# Power.net
KiCad netlist of a schematic drawn in Altium Designer
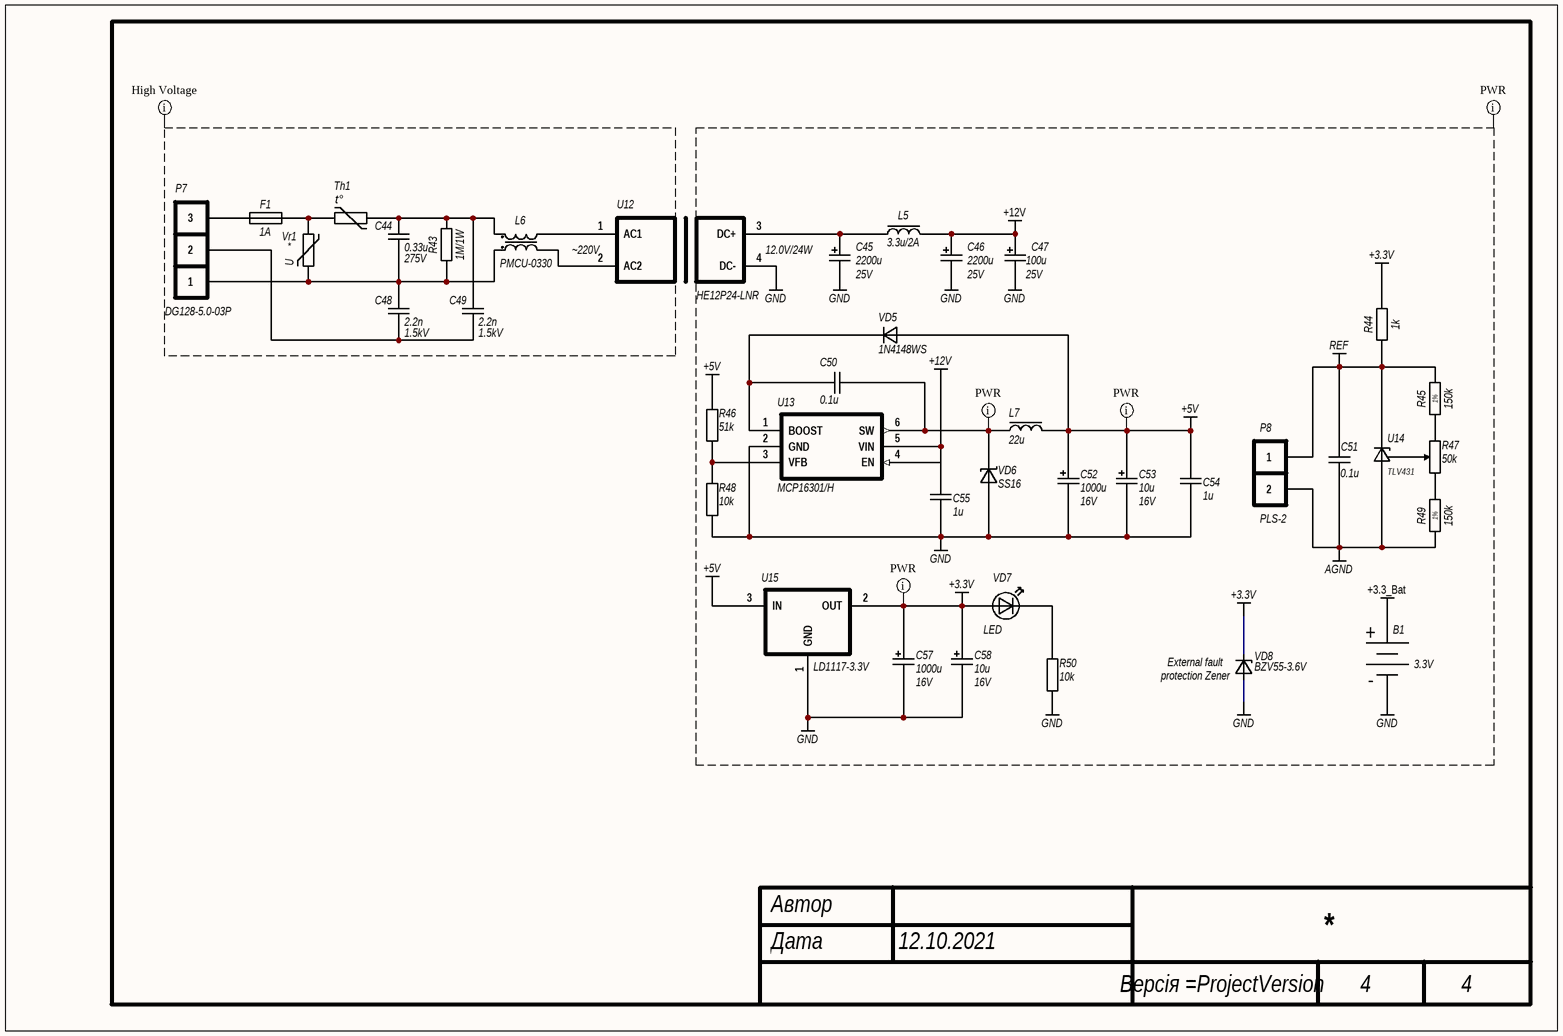
[diagram p0: Power.SchDoc]

(export (version "E")
  (design (tool "Eeschema 10.0.6"))
  (components
    (comp (ref "B1")
      (value "3.3V")
      (footprint "BH810")
      (description "Battery holder CR2032 (3.3В)")
      (libsource (lib "Passive") (part "Battery Holder"))
    )
    (comp (ref "C44")
      (value "0.33u")
      (footprint "MER 13x5.5 h10 R10.16")
      (fields (field (name "VOLTAGE") "275V"))
      (libsource (lib "Passive") (part "Capasitor"))
    )
    (comp (ref "C45")
      (value "2200u")
      (footprint "El-d13-h25-F5-0.6")
      (fields (field (name "VOLTAGE") "25V"))
      (libsource (lib "Passive") (part "Capasitor POL"))
    )
    (comp (ref "C46")
      (value "2200u")
      (footprint "El-d13-h25-F5-0.6")
      (fields (field (name "VOLTAGE") "25V"))
      (libsource (lib "Passive") (part "Capasitor POL"))
    )
    (comp (ref "C47")
      (value "100u")
      (footprint "EL Case A (3216-18)")
      (fields (field (name "VOLTAGE") "25V"))
      (libsource (lib "Passive") (part "Capasitor TECAP"))
    )
    (comp (ref "C48")
      (value "2.2n")
      (footprint "MER 13x5.5 h10 R10.16")
      (fields (field (name "VOLTAGE") "1.5kV"))
      (libsource (lib "Passive") (part "Capasitor"))
    )
    (comp (ref "C49")
      (value "2.2n")
      (footprint "MER 13x5.5 h10 R10.16")
      (fields (field (name "VOLTAGE") "1.5kV"))
      (libsource (lib "Passive") (part "Capasitor"))
    )
    (comp (ref "C50")
      (value "0.1u")
      (footprint "C0603(1608)")
      (libsource (lib "Passive") (part "Capasitor SMD"))
    )
    (comp (ref "C51")
      (value "0.1u")
      (footprint "C0603(1608)")
      (libsource (lib "Passive") (part "Capasitor SMD"))
    )
    (comp (ref "C52")
      (value "1000u")
      (footprint "El-d10-h16-F5-0.6")
      (fields (field (name "VOLTAGE") "16V"))
      (libsource (lib "Passive") (part "Capasitor POL"))
    )
    (comp (ref "C53")
      (value "10u")
      (footprint "EL Case A (3216-18)")
      (fields (field (name "VOLTAGE") "16V"))
      (libsource (lib "Passive") (part "Capasitor TECAP"))
    )
    (comp (ref "C54")
      (value "1u")
      (footprint "C0603(1608)")
      (libsource (lib "Passive") (part "Capasitor SMD"))
    )
    (comp (ref "C55")
      (value "1u")
      (footprint "C0603(1608)")
      (libsource (lib "Passive") (part "Capasitor SMD"))
    )
    (comp (ref "C57")
      (value "1000u")
      (footprint "El-d10-h16-F5-0.6")
      (fields (field (name "VOLTAGE") "16V"))
      (libsource (lib "Passive") (part "Capasitor POL"))
    )
    (comp (ref "C58")
      (value "10u")
      (footprint "EL Case A (3216-18)")
      (fields (field (name "VOLTAGE") "16V"))
      (libsource (lib "Passive") (part "Capasitor TECAP"))
    )
    (comp (ref "F1") (value "1A") (footprint "562 Series") (libsource (lib "Passive") (part "Fuse")))
    (comp (ref "L5") (value "3.3u/2A") (footprint "DR-CW8A") (libsource (lib "") (part "Inductor_1")))
    (comp (ref "L6") (value "~") (footprint "PMCU-0330") (libsource (lib "Passive") (part "Chocke Inductor")))
    (comp (ref "L7") (value "22u") (footprint "CDRH6D28") (libsource (lib "Passive") (part "Inductor")))
    (comp (ref "P7")
      (value "DG128-5.0-03P")
      (footprint "DG128-5.0-03P")
      (description "20A/300V AC 5mm")
      (libsource (lib "Connector") (part "DG128-5.0-03P"))
    )
    (comp (ref "P8") (value "PLS-2") (footprint "PLS-2") (libsource (lib "Connector") (part "PLS-2")))
    (comp (ref "R43")
      (value "1M/1W")
      (footprint "RES1016-650X250")
      (libsource (lib "Passive") (part "Resistor THD"))
    )
    (comp (ref "R44") (value "1k") (footprint "R0603") (libsource (lib "Passive") (part "Resistor SMD")))
    (comp (ref "R45")
      (value "150k")
      (footprint "R0603")
      (fields (field (name "ACCURACY") "1%"))
      (libsource (lib "Passive") (part "Resistor SMD"))
    )
    (comp (ref "R46") (value "51k") (footprint "R0603") (libsource (lib "Passive") (part "Resistor SMD")))
    (comp (ref "R47")
      (value "50k")
      (footprint "T910W (3296W)")
      (libsource (lib "Passive") (part "Trimming Resistor"))
    )
    (comp (ref "R48") (value "10k") (footprint "R0603") (libsource (lib "Passive") (part "Resistor SMD")))
    (comp (ref "R49")
      (value "150k")
      (footprint "R0603")
      (fields (field (name "ACCURACY") "1%"))
      (libsource (lib "Passive") (part "Resistor SMD"))
    )
    (comp (ref "R50") (value "10k") (footprint "R0603") (libsource (lib "Passive") (part "Resistor SMD")))
    (comp (ref "Th1") (value "~") (footprint "TH D13 7.5b") (libsource (lib "Passive") (part "Thermistor")))
    (comp (ref "U12")
      (value "HE12P24-LNR")
      (footprint "HExxPyy-LRN")
      (fields (field (name "OUT") "12.0V/24W") (field (name "IN") "~220V"))
      (libsource (lib "Power") (part "HE12P24-LNR"))
    )
    (comp (ref "U13")
      (value "MCP16301/H")
      (footprint "SOT23-6")
      (libsource (lib "Power") (part "MCP16301/H"))
    )
    (comp (ref "U14") (value "TLV431") (footprint "SOT23") (libsource (lib "Diode") (part "TL431")))
    (comp (ref "U15") (value "LD1117-3.3V") (footprint "SOT223") (libsource (lib "Power") (part "LD1117")))
    (comp (ref "VD5")
      (value "1N4148WS")
      (footprint "SOD323")
      (description "SOD323 100V 200mA")
      (libsource (lib "Diode") (part "1N4148WS"))
    )
    (comp (ref "VD6")
      (value "SS16")
      (footprint "DO-214AC (SMA)")
      (description "SMA (DO214AC) Schottky 60V 1A")
      (libsource (lib "Diode") (part "SS16"))
    )
    (comp (ref "VD7") (value "LED") (footprint "SMD_0805_GREEN") (libsource (lib "Diode") (part "LED")))
    (comp (ref "VD8")
      (value "BZV55-3.6V")
      (footprint "SOD80C")
      (description "SOD80C 250mA")
      (fields (field (name "VOLTAGE") "3.6V"))
      (libsource (lib "Diode") (part "BZV55"))
    )
    (comp (ref "Vr1") (value "*") (footprint "VAR-10K-5.6") (libsource (lib "Passive") (part "Varistor")))
  )
  (nets
    (net (code "1") (name "+3.3V") (class "Default")
      (node (ref "C57") (pin "1") (pinfunction "1_1") (pintype "passive"))
      (node (ref "C58") (pin "1") (pinfunction "1_1") (pintype "passive"))
      (node (ref "R44") (pin "2") (pinfunction "2_2") (pintype "passive"))
      (node (ref "U15") (pin "2") (pinfunction "OUT_2") (pintype "power_in"))
      (node (ref "VD7") (pin "1") (pinfunction "A_1") (pintype "passive"))
      (node (ref "VD8") (pin "2") (pinfunction "K_2") (pintype "passive"))
    )
    (net (code "2") (name "+3.3_Bat") (class "Default")
      (node (ref "B1") (pin "1") (pinfunction "1_1") (pintype "passive"))
    )
    (net (code "3") (name "+5V") (class "Default")
      (node (ref "C52") (pin "1") (pinfunction "1_1") (pintype "passive"))
      (node (ref "C53") (pin "1") (pinfunction "1_1") (pintype "passive"))
      (node (ref "C54") (pin "1") (pinfunction "1_1") (pintype "passive"))
      (node (ref "L7") (pin "2") (pinfunction "2_2") (pintype "passive"))
      (node (ref "R46") (pin "2") (pinfunction "2_2") (pintype "passive"))
      (node (ref "U15") (pin "3") (pinfunction "IN_3") (pintype "power_in"))
      (node (ref "VD5") (pin "1") (pinfunction "A_1") (pintype "passive"))
    )
    (net (code "4") (name "+12V") (class "Default")
      (node (ref "C46") (pin "1") (pinfunction "1_1") (pintype "passive"))
      (node (ref "C47") (pin "1") (pinfunction "1_1") (pintype "passive"))
      (node (ref "C55") (pin "1") (pinfunction "1_1") (pintype "passive"))
      (node (ref "L5") (pin "2") (pinfunction "2_2") (pintype "passive"))
      (node (ref "U13") (pin "4") (pinfunction "EN_4") (pintype "input"))
      (node (ref "U13") (pin "5") (pinfunction "VIN_5") (pintype "power_in"))
    )
    (net (code "5") (name "AGND") (class "Default")
      (node (ref "C51") (pin "1") (pinfunction "1_1") (pintype "passive"))
      (node (ref "P8") (pin "2") (pinfunction "2_2") (pintype "passive"))
      (node (ref "R49") (pin "1") (pinfunction "1_1") (pintype "passive"))
      (node (ref "U14") (pin "1") (pinfunction "A_1") (pintype "passive"))
    )
    (net (code "6") (name "GND") (class "Default")
      (node (ref "B1") (pin "2") (pinfunction "2_2") (pintype "passive"))
      (node (ref "C45") (pin "2") (pinfunction "2_2") (pintype "passive"))
      (node (ref "C46") (pin "2") (pinfunction "2_2") (pintype "passive"))
      (node (ref "C47") (pin "2") (pinfunction "2_2") (pintype "passive"))
      (node (ref "C52") (pin "2") (pinfunction "2_2") (pintype "passive"))
      (node (ref "C53") (pin "2") (pinfunction "2_2") (pintype "passive"))
      (node (ref "C54") (pin "2") (pinfunction "2_2") (pintype "passive"))
      (node (ref "C55") (pin "2") (pinfunction "2_2") (pintype "passive"))
      (node (ref "C57") (pin "2") (pinfunction "2_2") (pintype "passive"))
      (node (ref "C58") (pin "2") (pinfunction "2_2") (pintype "passive"))
      (node (ref "R48") (pin "1") (pinfunction "1_1") (pintype "passive"))
      (node (ref "R50") (pin "1") (pinfunction "1_1") (pintype "passive"))
      (node (ref "U12") (pin "4") (pinfunction "DC-_4") (pintype "passive"))
      (node (ref "U13") (pin "2") (pinfunction "GND_2") (pintype "power_in"))
      (node (ref "U15") (pin "1") (pinfunction "GND_1") (pintype "power_in"))
      (node (ref "VD6") (pin "1") (pinfunction "A_1") (pintype "passive"))
      (node (ref "VD8") (pin "1") (pinfunction "A_1") (pintype "passive"))
    )
    (net (code "7") (name "Net-(C44-Pad1)") (class "Default")
      (node (ref "C44") (pin "1") (pinfunction "1_1") (pintype "passive"))
      (node (ref "C48") (pin "2") (pinfunction "2_2") (pintype "passive"))
      (node (ref "L6") (pin "2") (pinfunction "2_2") (pintype "passive"))
      (node (ref "P7") (pin "1") (pinfunction "1_1") (pintype "passive"))
      (node (ref "R43") (pin "1") (pinfunction "1_1") (pintype "passive"))
      (node (ref "Vr1") (pin "1") (pinfunction "1_1") (pintype "passive"))
    )
    (net (code "8") (name "Net-(C44-Pad2)") (class "Default")
      (node (ref "C44") (pin "2") (pinfunction "2_2") (pintype "passive"))
      (node (ref "C49") (pin "2") (pinfunction "2_2") (pintype "passive"))
      (node (ref "L6") (pin "1") (pinfunction "1_1") (pintype "passive"))
      (node (ref "R43") (pin "2") (pinfunction "2_2") (pintype "passive"))
      (node (ref "Th1") (pin "2") (pinfunction "2_2") (pintype "passive"))
    )
    (net (code "9") (name "Net-(C48-Pad1)") (class "Default")
      (node (ref "C48") (pin "1") (pinfunction "1_1") (pintype "passive"))
      (node (ref "C49") (pin "1") (pinfunction "1_1") (pintype "passive"))
      (node (ref "P7") (pin "2") (pinfunction "2_2") (pintype "passive"))
    )
    (net (code "10") (name "Net-(F1-Pad1)") (class "Default")
      (node (ref "F1") (pin "1") (pinfunction "1_1") (pintype "passive"))
      (node (ref "P7") (pin "3") (pinfunction "3_3") (pintype "passive"))
    )
    (net (code "11") (name "Net-(F1-Pad2)") (class "Default")
      (node (ref "F1") (pin "2") (pinfunction "2_2") (pintype "passive"))
      (node (ref "Th1") (pin "1") (pinfunction "1_1") (pintype "passive"))
      (node (ref "Vr1") (pin "2") (pinfunction "2_2") (pintype "passive"))
    )
    (net (code "12") (name "Net-(R45-Pad1)") (class "Default")
      (node (ref "R45") (pin "1") (pinfunction "1_1") (pintype "passive"))
      (node (ref "R47") (pin "3") (pinfunction "3_3") (pintype "passive"))
    )
    (net (code "13") (name "Net-(R47-Pad1)") (class "Default")
      (node (ref "R47") (pin "1") (pinfunction "1_1") (pintype "passive"))
      (node (ref "R49") (pin "2") (pinfunction "2_2") (pintype "passive"))
    )
    (net (code "14") (name "Net-(U12-AC1)") (class "Default")
      (node (ref "L6") (pin "4") (pinfunction "4_4") (pintype "passive"))
      (node (ref "U12") (pin "1") (pinfunction "AC1_1") (pintype "passive"))
    )
    (net (code "15") (name "Net-(U12-AC2)") (class "Default")
      (node (ref "L6") (pin "3") (pinfunction "3_3") (pintype "passive"))
      (node (ref "U12") (pin "2") (pinfunction "AC2_2") (pintype "passive"))
    )
    (net (code "16") (name "Net-(U12-DC+)") (class "Default")
      (node (ref "C45") (pin "1") (pinfunction "1_1") (pintype "passive"))
      (node (ref "L5") (pin "1") (pinfunction "1_1") (pintype "passive"))
      (node (ref "U12") (pin "3") (pinfunction "DC+_3") (pintype "passive"))
    )
    (net (code "17") (name "Net-(U13-BOOST)") (class "Default")
      (node (ref "C50") (pin "1") (pinfunction "1_1") (pintype "passive"))
      (node (ref "U13") (pin "1") (pinfunction "BOOST_1") (pintype "passive"))
      (node (ref "VD5") (pin "2") (pinfunction "K_2") (pintype "passive"))
    )
    (net (code "18") (name "Net-(U13-SW)") (class "Default")
      (node (ref "C50") (pin "2") (pinfunction "2_2") (pintype "passive"))
      (node (ref "L7") (pin "1") (pinfunction "1_1") (pintype "passive"))
      (node (ref "U13") (pin "6") (pinfunction "SW_6") (pintype "output"))
      (node (ref "VD6") (pin "2") (pinfunction "K_2") (pintype "passive"))
    )
    (net (code "19") (name "Net-(U13-VFB)") (class "Default")
      (node (ref "R46") (pin "1") (pinfunction "1_1") (pintype "passive"))
      (node (ref "R48") (pin "2") (pinfunction "2_2") (pintype "passive"))
      (node (ref "U13") (pin "3") (pinfunction "VFB_3") (pintype "passive"))
    )
    (net (code "20") (name "Net-(U14-Adj)") (class "Default")
      (node (ref "R47") (pin "2") (pinfunction "2_2") (pintype "passive"))
      (node (ref "U14") (pin "3") (pinfunction "Adj_3") (pintype "passive"))
    )
    (net (code "21") (name "Net-(VD7-K)") (class "Default")
      (node (ref "R50") (pin "2") (pinfunction "2_2") (pintype "passive"))
      (node (ref "VD7") (pin "2") (pinfunction "K_2") (pintype "passive"))
    )
    (net (code "22") (name "REF") (class "Default")
      (node (ref "C51") (pin "2") (pinfunction "2_2") (pintype "passive"))
      (node (ref "P8") (pin "1") (pinfunction "1_1") (pintype "passive"))
      (node (ref "R44") (pin "1") (pinfunction "1_1") (pintype "passive"))
      (node (ref "R45") (pin "2") (pinfunction "2_2") (pintype "passive"))
      (node (ref "U14") (pin "2") (pinfunction "K_2") (pintype "passive"))
    )
  )
)
